# isolator.net
KiCad netlist of a schematic drawn in EAGLE
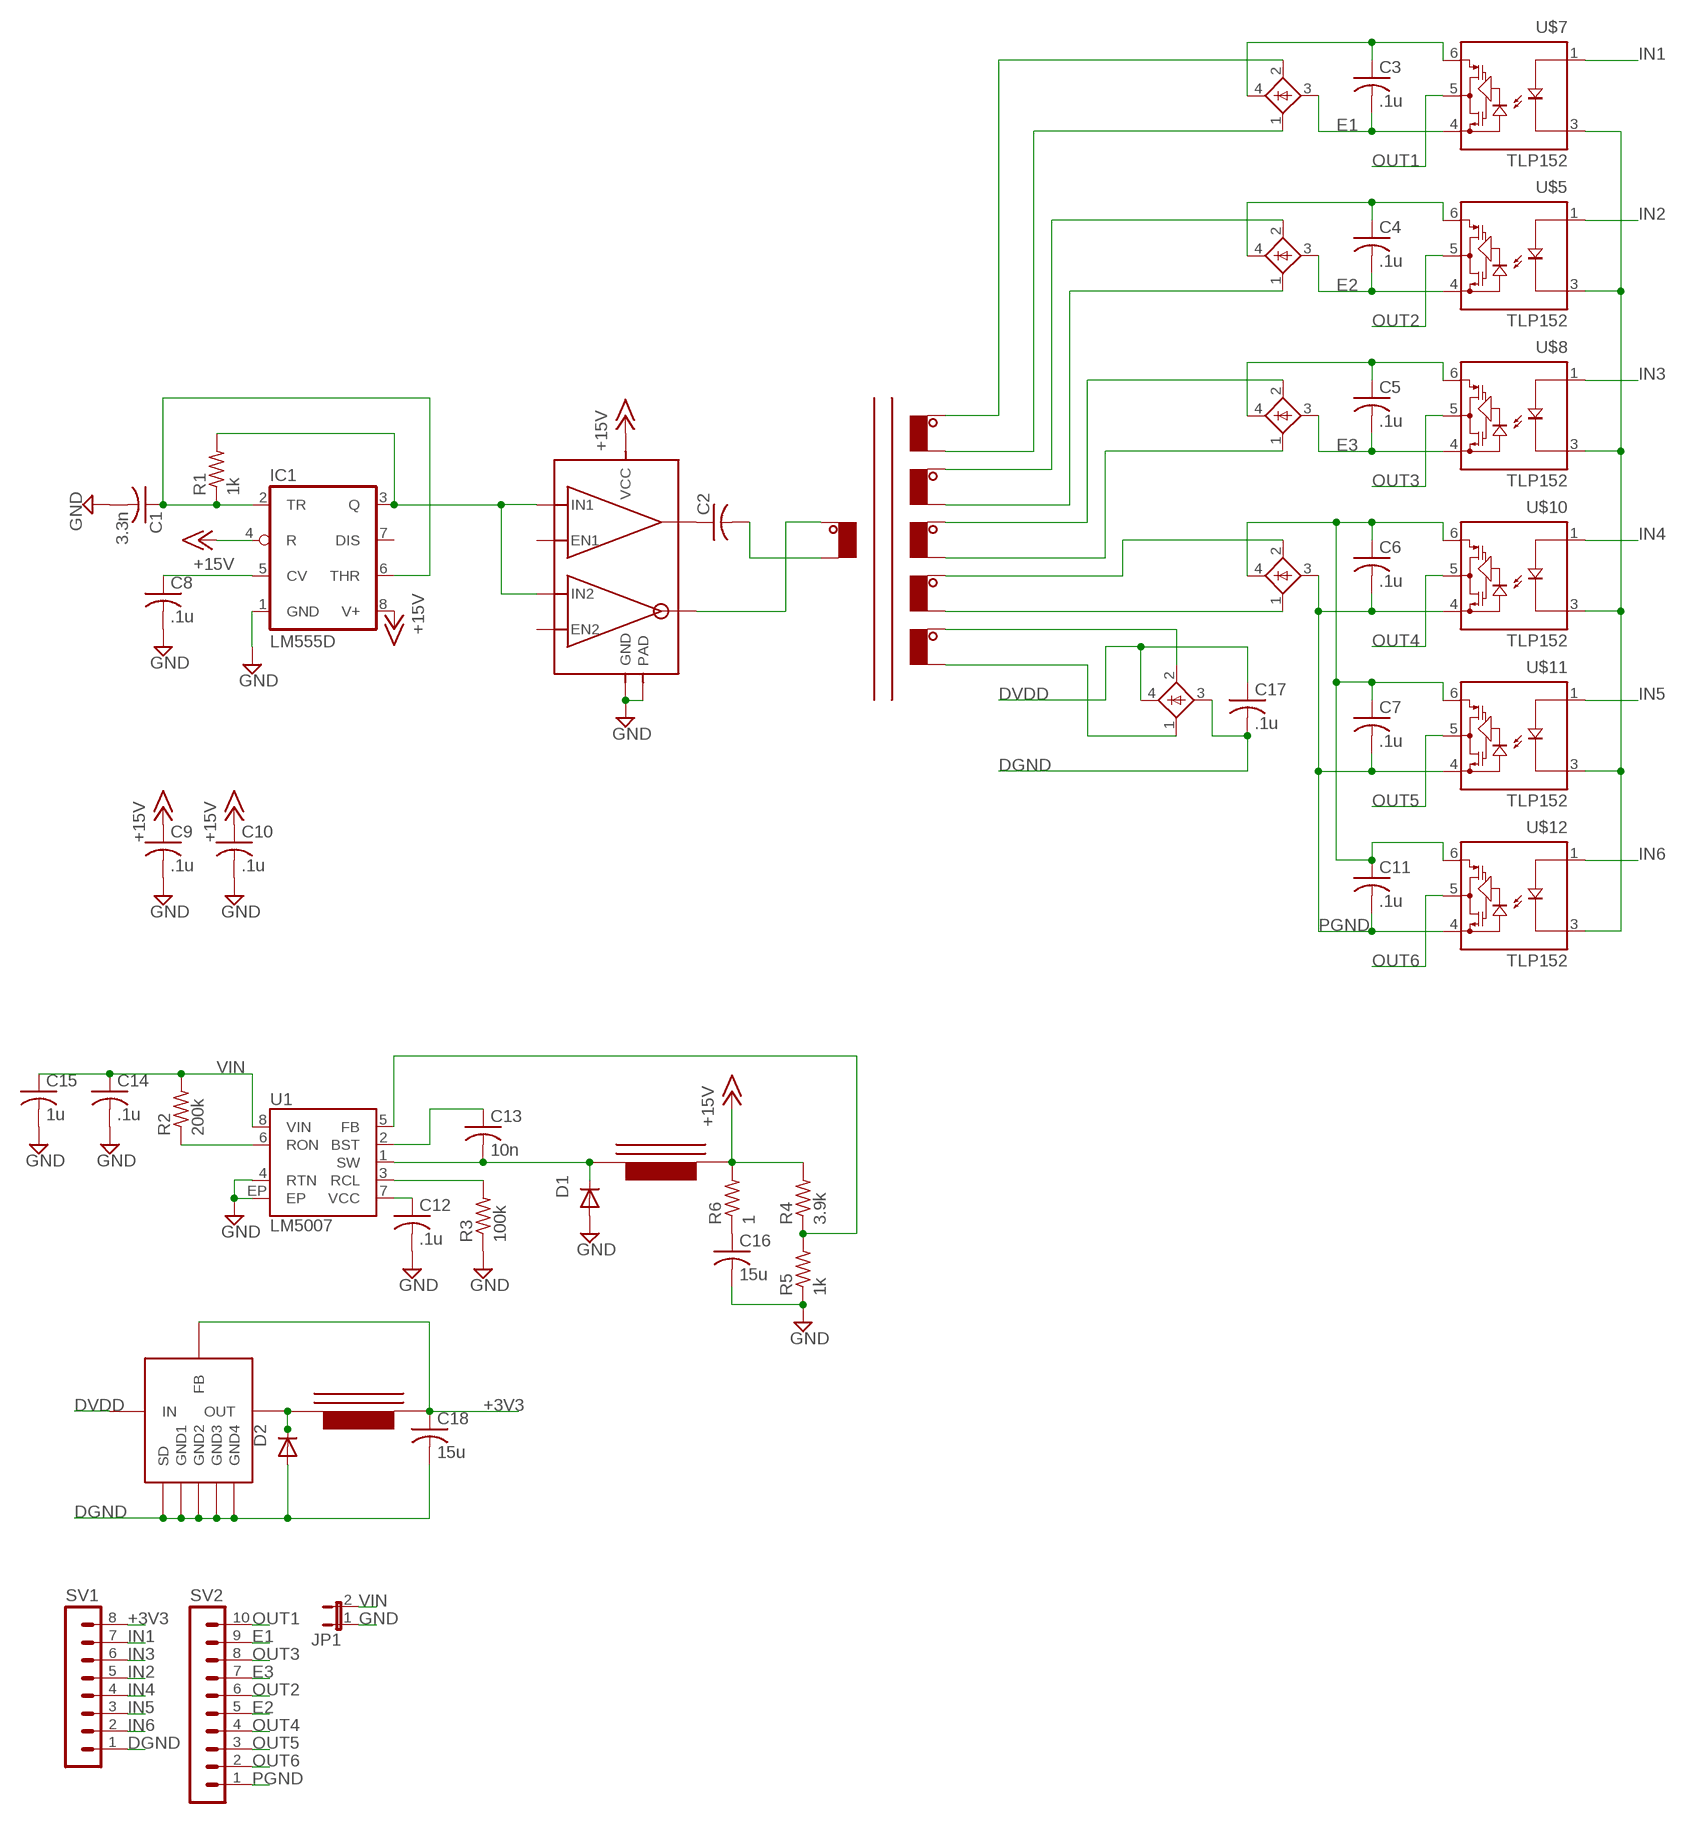
[diagram p0: schematic, sheet 1]
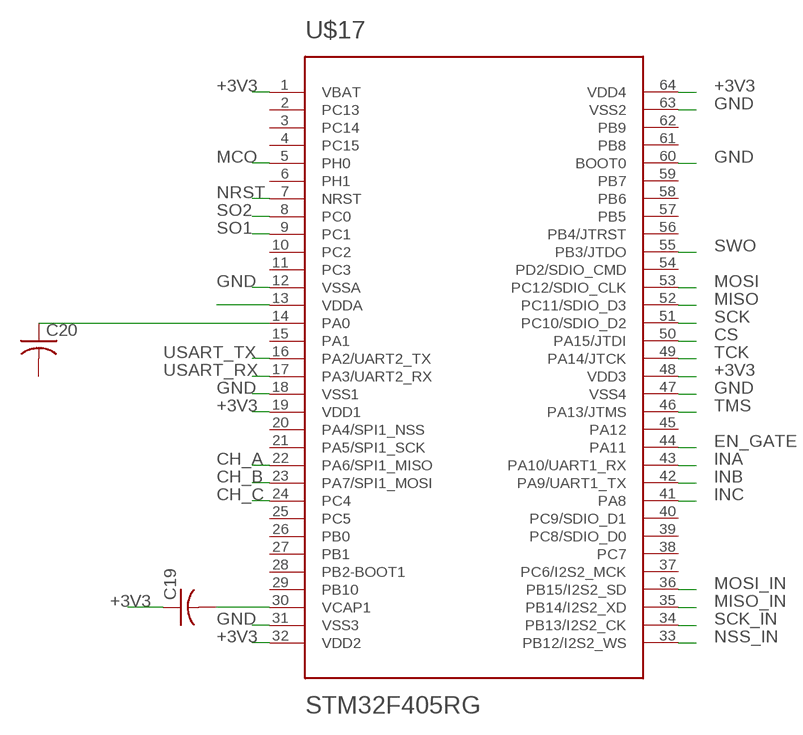
[diagram p1: schematic, sheet 2]

(export (version "E")
  (design (tool "Eeschema 10.0.6"))
  (components
    (comp (ref "C1")
      (value "3.3n")
      (footprint "eagle-import:C0805K")
      (libsource (lib "eagle-import") (part "rcl_C-USC0805K"))
    )
    (comp (ref "C2")
      (value "C-USC0805K")
      (footprint "eagle-import:C0805K")
      (libsource (lib "eagle-import") (part "rcl_C-USC0805K"))
    )
    (comp (ref "C3")
      (value ".1u")
      (footprint "eagle-import:C0805K")
      (libsource (lib "eagle-import") (part "rcl_C-USC0805K"))
    )
    (comp (ref "C4")
      (value ".1u")
      (footprint "eagle-import:C0805K")
      (libsource (lib "eagle-import") (part "rcl_C-USC0805K"))
    )
    (comp (ref "C5")
      (value ".1u")
      (footprint "eagle-import:C0805K")
      (libsource (lib "eagle-import") (part "rcl_C-USC0805K"))
    )
    (comp (ref "C6")
      (value ".1u")
      (footprint "eagle-import:C0805K")
      (libsource (lib "eagle-import") (part "rcl_C-USC0805K"))
    )
    (comp (ref "C7")
      (value ".1u")
      (footprint "eagle-import:C0805K")
      (libsource (lib "eagle-import") (part "rcl_C-USC0805K"))
    )
    (comp (ref "C8")
      (value ".1u")
      (footprint "eagle-import:C0805K")
      (libsource (lib "eagle-import") (part "rcl_C-USC0805K"))
    )
    (comp (ref "C9")
      (value ".1u")
      (footprint "eagle-import:C0805K")
      (libsource (lib "eagle-import") (part "rcl_C-USC0805K"))
    )
    (comp (ref "C10")
      (value ".1u")
      (footprint "eagle-import:C0805K")
      (libsource (lib "eagle-import") (part "rcl_C-USC0805K"))
    )
    (comp (ref "C11")
      (value ".1u")
      (footprint "eagle-import:C0805K")
      (libsource (lib "eagle-import") (part "rcl_C-USC0805K"))
    )
    (comp (ref "C12")
      (value ".1u")
      (footprint "eagle-import:C0805K")
      (libsource (lib "eagle-import") (part "rcl_C-USC0805K"))
    )
    (comp (ref "C13")
      (value "10n")
      (footprint "eagle-import:C0805K")
      (libsource (lib "eagle-import") (part "rcl_C-USC0805K"))
    )
    (comp (ref "C14")
      (value ".1u")
      (footprint "eagle-import:C0805K")
      (libsource (lib "eagle-import") (part "rcl_C-USC0805K"))
    )
    (comp (ref "C15")
      (value "1u")
      (footprint "eagle-import:C0805K")
      (libsource (lib "eagle-import") (part "rcl_C-USC0805K"))
    )
    (comp (ref "C16")
      (value "15u")
      (footprint "eagle-import:C0805K")
      (libsource (lib "eagle-import") (part "rcl_C-USC0805K"))
    )
    (comp (ref "C17")
      (value ".1u")
      (footprint "eagle-import:C0805K")
      (libsource (lib "eagle-import") (part "rcl_C-USC0805K"))
    )
    (comp (ref "C18")
      (value "15u")
      (footprint "eagle-import:C0805K")
      (libsource (lib "eagle-import") (part "rcl_C-USC0805K"))
    )
    (comp (ref "D1")
      (value "B170-13-F")
      (footprint "eagle-import:DO214AC")
      (libsource (lib "eagle-import") (part "DIODE-DO214AC"))
    )
    (comp (ref "D2")
      (value "B170-13-F")
      (footprint "eagle-import:DO214AC")
      (libsource (lib "eagle-import") (part "DIODE-DO214AC"))
    )
    (comp (ref "IC1")
      (value "LM555D")
      (footprint "eagle-import:SO08")
      (libsource (lib "eagle-import") (part "555DLM"))
    )
    (comp (ref "JP1")
      (value "JP1E")
      (footprint "eagle-import:JP1")
      (libsource (lib "eagle-import") (part "JP1E"))
    )
    (comp (ref "R1")
      (value "1k")
      (footprint "eagle-import:M0805")
      (libsource (lib "eagle-import") (part "R-US_M0805"))
    )
    (comp (ref "R2")
      (value "200k")
      (footprint "eagle-import:M0805")
      (libsource (lib "eagle-import") (part "R-US_M0805"))
    )
    (comp (ref "R3")
      (value "100k")
      (footprint "eagle-import:M0805")
      (libsource (lib "eagle-import") (part "R-US_M0805"))
    )
    (comp (ref "R4")
      (value "3.9k")
      (footprint "eagle-import:M0805")
      (libsource (lib "eagle-import") (part "R-US_M0805"))
    )
    (comp (ref "R5")
      (value "1k")
      (footprint "eagle-import:M0805")
      (libsource (lib "eagle-import") (part "R-US_M0805"))
    )
    (comp (ref "R6")
      (value "1")
      (footprint "eagle-import:M0805")
      (libsource (lib "eagle-import") (part "R-US_M0805"))
    )
    (comp (ref "SV1")
      (value "MA08-1")
      (footprint "eagle-import:MA08-1")
      (libsource (lib "eagle-import") (part "MA08-1"))
    )
    (comp (ref "SV2")
      (value "MA10-1")
      (footprint "eagle-import:MA10-1")
      (libsource (lib "eagle-import") (part "MA10-1"))
    )
    (comp (ref "U$1")
      (value "HP1")
      (footprint "eagle-import:HP1")
      (libsource (lib "eagle-import") (part "HP1"))
    )
    (comp (ref "U$2")
      (value "UCC27525DGN")
      (footprint "eagle-import:HTSSOP8DGN")
      (libsource (lib "eagle-import") (part "UCC27525DGN"))
    )
    (comp (ref "U$3")
      (value "BAS4002A")
      (footprint "eagle-import:SOT-143")
      (libsource (lib "eagle-import") (part "BAS4002A"))
    )
    (comp (ref "U$4")
      (value "BAS4002A")
      (footprint "eagle-import:SOT-143")
      (libsource (lib "eagle-import") (part "BAS4002A"))
    )
    (comp (ref "U$5")
      (value "TLP152")
      (footprint "eagle-import:DIP5-SMD")
      (libsource (lib "eagle-import") (part "TLP152"))
    )
    (comp (ref "U$6")
      (value "BAS4002A")
      (footprint "eagle-import:SOT-143")
      (libsource (lib "eagle-import") (part "BAS4002A"))
    )
    (comp (ref "U$7")
      (value "TLP152")
      (footprint "eagle-import:DIP5-SMD")
      (libsource (lib "eagle-import") (part "TLP152"))
    )
    (comp (ref "U$8")
      (value "TLP152")
      (footprint "eagle-import:DIP5-SMD")
      (libsource (lib "eagle-import") (part "TLP152"))
    )
    (comp (ref "U$9")
      (value "BAS4002A")
      (footprint "eagle-import:SOT-143")
      (libsource (lib "eagle-import") (part "BAS4002A"))
    )
    (comp (ref "U$10")
      (value "TLP152")
      (footprint "eagle-import:DIP5-SMD")
      (libsource (lib "eagle-import") (part "TLP152"))
    )
    (comp (ref "U$11")
      (value "TLP152")
      (footprint "eagle-import:DIP5-SMD")
      (libsource (lib "eagle-import") (part "TLP152"))
    )
    (comp (ref "U$12")
      (value "TLP152")
      (footprint "eagle-import:DIP5-SMD")
      (libsource (lib "eagle-import") (part "TLP152"))
    )
    (comp (ref "U$13")
      (value "SRN6045-101M")
      (footprint "eagle-import:SRN6045")
      (libsource (lib "eagle-import") (part "SRN6045-101M"))
    )
    (comp (ref "U$14")
      (value "BAS4002A")
      (footprint "eagle-import:SOT-143")
      (libsource (lib "eagle-import") (part "BAS4002A"))
    )
    (comp (ref "U$15")
      (value "AP1509")
      (footprint "eagle-import:SO8")
      (libsource (lib "eagle-import") (part "AP1509"))
    )
    (comp (ref "U$16")
      (value "SRN6045-101M")
      (footprint "eagle-import:SRN6045")
      (libsource (lib "eagle-import") (part "SRN6045-101M"))
    )
    (comp (ref "U1")
      (value "LM5007")
      (footprint "eagle-import:MSOP-8-EP")
      (libsource (lib "eagle-import") (part "LM5007"))
    )
    (comp (ref "C19")
      (value "C-USC0805K")
      (footprint "eagle-import:C0805K")
      (libsource (lib "eagle-import") (part "C-USC0805K"))
    )
    (comp (ref "C20")
      (value "C-USC0805K")
      (footprint "eagle-import:C0805K")
      (libsource (lib "eagle-import") (part "C-USC0805K"))
    )
    (comp (ref "U$17")
      (value "STM32F405RG")
      (footprint "eagle-import:TQFP64")
      (libsource (lib "eagle-import") (part "STM32F405RG"))
    )
  )
  (nets
    (net (code "1") (name "+3V3") (class "Default")
      (node (ref "C18") (pin "1") (pinfunction "1_1") (pintype "passive"))
      (node (ref "C19") (pin "1") (pinfunction "1_1") (pintype "passive"))
      (node (ref "SV1") (pin "8") (pinfunction "8_8") (pintype "passive"))
      (node (ref "U$15") (pin "3") (pinfunction "FB_3") (pintype "bidirectional"))
      (node (ref "U$16") (pin "P$2") (pinfunction "P$2_P$2") (pintype "bidirectional"))
      (node (ref "U$17") (pin "1") (pinfunction "VBAT_1") (pintype "bidirectional"))
      (node (ref "U$17") (pin "19") (pinfunction "VDD1_19") (pintype "bidirectional"))
      (node (ref "U$17") (pin "32") (pinfunction "VDD2_32") (pintype "bidirectional"))
      (node (ref "U$17") (pin "48") (pinfunction "VDD3_48") (pintype "bidirectional"))
      (node (ref "U$17") (pin "64") (pinfunction "VDD4_64") (pintype "bidirectional"))
    )
    (net (code "2") (name "+15V") (class "Default")
      (node (ref "C10") (pin "1") (pinfunction "1_1") (pintype "passive"))
      (node (ref "C9") (pin "1") (pinfunction "1_1") (pintype "passive"))
      (node (ref "IC1") (pin "4") (pinfunction "R_4") (pintype "input"))
      (node (ref "IC1") (pin "8") (pinfunction "V+_8") (pintype "power_in"))
      (node (ref "R4") (pin "2") (pinfunction "2_2") (pintype "passive"))
      (node (ref "R6") (pin "2") (pinfunction "2_2") (pintype "passive"))
      (node (ref "U$13") (pin "P$2") (pinfunction "P$2_P$2") (pintype "bidirectional"))
      (node (ref "U$2") (pin "6") (pinfunction "VCC_6") (pintype "bidirectional"))
    )
    (net (code "3") (name "CH_A") (class "Default")
      (node (ref "U$17") (pin "22") (pinfunction "PA6/SPI1_MISO_22") (pintype "bidirectional"))
    )
    (net (code "4") (name "CH_B") (class "Default")
      (node (ref "U$17") (pin "23") (pinfunction "PA7/SPI1_MOSI_23") (pintype "bidirectional"))
    )
    (net (code "5") (name "CH_C") (class "Default")
      (node (ref "U$17") (pin "24") (pinfunction "PC4_24") (pintype "bidirectional"))
    )
    (net (code "6") (name "CS") (class "Default")
      (node (ref "U$17") (pin "50") (pinfunction "PA15/JTDI_50") (pintype "bidirectional"))
    )
    (net (code "7") (name "DGND") (class "Default")
      (node (ref "C17") (pin "2") (pinfunction "2_2") (pintype "passive"))
      (node (ref "C18") (pin "2") (pinfunction "2_2") (pintype "passive"))
      (node (ref "D2") (pin "A") (pinfunction "A_A") (pintype "passive"))
      (node (ref "SV1") (pin "1") (pinfunction "1_1") (pintype "passive"))
      (node (ref "U$10") (pin "3") (pinfunction "LED-_3") (pintype "passive"))
      (node (ref "U$11") (pin "3") (pinfunction "LED-_3") (pintype "passive"))
      (node (ref "U$12") (pin "3") (pinfunction "LED-_3") (pintype "passive"))
      (node (ref "U$14") (pin "3") (pinfunction "-_3") (pintype "passive"))
      (node (ref "U$15") (pin "4") (pinfunction "SD_4") (pintype "bidirectional"))
      (node (ref "U$15") (pin "5") (pinfunction "GND1_5") (pintype "bidirectional"))
      (node (ref "U$15") (pin "6") (pinfunction "GND2_6") (pintype "bidirectional"))
      (node (ref "U$15") (pin "7") (pinfunction "GND3_7") (pintype "bidirectional"))
      (node (ref "U$15") (pin "8") (pinfunction "GND4_8") (pintype "bidirectional"))
      (node (ref "U$5") (pin "3") (pinfunction "LED-_3") (pintype "passive"))
      (node (ref "U$7") (pin "3") (pinfunction "LED-_3") (pintype "passive"))
      (node (ref "U$8") (pin "3") (pinfunction "LED-_3") (pintype "passive"))
    )
    (net (code "8") (name "DVDD") (class "Default")
      (node (ref "C17") (pin "1") (pinfunction "1_1") (pintype "passive"))
      (node (ref "U$14") (pin "4") (pinfunction "+_4") (pintype "passive"))
      (node (ref "U$15") (pin "1") (pinfunction "IN_1") (pintype "bidirectional"))
    )
    (net (code "9") (name "E1") (class "Default")
      (node (ref "C3") (pin "2") (pinfunction "2_2") (pintype "passive"))
      (node (ref "SV2") (pin "9") (pinfunction "9_9") (pintype "passive"))
      (node (ref "U$3") (pin "3") (pinfunction "-_3") (pintype "passive"))
      (node (ref "U$7") (pin "4") (pinfunction "GND_4") (pintype "passive"))
    )
    (net (code "10") (name "E2") (class "Default")
      (node (ref "C4") (pin "2") (pinfunction "2_2") (pintype "passive"))
      (node (ref "SV2") (pin "5") (pinfunction "5_5") (pintype "passive"))
      (node (ref "U$4") (pin "3") (pinfunction "-_3") (pintype "passive"))
      (node (ref "U$5") (pin "4") (pinfunction "GND_4") (pintype "passive"))
    )
    (net (code "11") (name "E3") (class "Default")
      (node (ref "C5") (pin "2") (pinfunction "2_2") (pintype "passive"))
      (node (ref "SV2") (pin "7") (pinfunction "7_7") (pintype "passive"))
      (node (ref "U$6") (pin "3") (pinfunction "-_3") (pintype "passive"))
      (node (ref "U$8") (pin "4") (pinfunction "GND_4") (pintype "passive"))
    )
    (net (code "12") (name "EN_GATE") (class "Default")
      (node (ref "U$17") (pin "44") (pinfunction "PA11_44") (pintype "bidirectional"))
    )
    (net (code "13") (name "GND") (class "Default")
      (node (ref "C1") (pin "2") (pinfunction "2_2") (pintype "passive"))
      (node (ref "C10") (pin "2") (pinfunction "2_2") (pintype "passive"))
      (node (ref "C12") (pin "2") (pinfunction "2_2") (pintype "passive"))
      (node (ref "C14") (pin "2") (pinfunction "2_2") (pintype "passive"))
      (node (ref "C15") (pin "2") (pinfunction "2_2") (pintype "passive"))
      (node (ref "C16") (pin "2") (pinfunction "2_2") (pintype "passive"))
      (node (ref "C8") (pin "2") (pinfunction "2_2") (pintype "passive"))
      (node (ref "C9") (pin "2") (pinfunction "2_2") (pintype "passive"))
      (node (ref "D1") (pin "A") (pinfunction "A_A") (pintype "passive"))
      (node (ref "IC1") (pin "1") (pinfunction "GND_1") (pintype "power_in"))
      (node (ref "JP1") (pin "1") (pinfunction "1_1") (pintype "passive"))
      (node (ref "R3") (pin "1") (pinfunction "1_1") (pintype "passive"))
      (node (ref "R5") (pin "1") (pinfunction "1_1") (pintype "passive"))
      (node (ref "U$17") (pin "12") (pinfunction "VSSA_12") (pintype "bidirectional"))
      (node (ref "U$17") (pin "18") (pinfunction "VSS1_18") (pintype "bidirectional"))
      (node (ref "U$17") (pin "31") (pinfunction "VSS3_31") (pintype "bidirectional"))
      (node (ref "U$17") (pin "47") (pinfunction "VSS4_47") (pintype "bidirectional"))
      (node (ref "U$17") (pin "60") (pinfunction "BOOT0_60") (pintype "bidirectional"))
      (node (ref "U$17") (pin "63") (pinfunction "VSS2_63") (pintype "bidirectional"))
      (node (ref "U$2") (pin "3") (pinfunction "GND_3") (pintype "bidirectional"))
      (node (ref "U$2") (pin "EXP") (pinfunction "PAD_EXP") (pintype "bidirectional"))
      (node (ref "U1") (pin "4") (pinfunction "RTN_4") (pintype "bidirectional"))
      (node (ref "U1") (pin "EP") (pinfunction "EP_EP") (pintype "bidirectional"))
    )
    (net (code "14") (name "IN1") (class "Default")
      (node (ref "SV1") (pin "7") (pinfunction "7_7") (pintype "passive"))
      (node (ref "U$7") (pin "1") (pinfunction "LED+_1") (pintype "passive"))
    )
    (net (code "15") (name "IN2") (class "Default")
      (node (ref "SV1") (pin "5") (pinfunction "5_5") (pintype "passive"))
      (node (ref "U$5") (pin "1") (pinfunction "LED+_1") (pintype "passive"))
    )
    (net (code "16") (name "IN3") (class "Default")
      (node (ref "SV1") (pin "6") (pinfunction "6_6") (pintype "passive"))
      (node (ref "U$8") (pin "1") (pinfunction "LED+_1") (pintype "passive"))
    )
    (net (code "17") (name "IN4") (class "Default")
      (node (ref "SV1") (pin "4") (pinfunction "4_4") (pintype "passive"))
      (node (ref "U$10") (pin "1") (pinfunction "LED+_1") (pintype "passive"))
    )
    (net (code "18") (name "IN5") (class "Default")
      (node (ref "SV1") (pin "3") (pinfunction "3_3") (pintype "passive"))
      (node (ref "U$11") (pin "1") (pinfunction "LED+_1") (pintype "passive"))
    )
    (net (code "19") (name "IN6") (class "Default")
      (node (ref "SV1") (pin "2") (pinfunction "2_2") (pintype "passive"))
      (node (ref "U$12") (pin "1") (pinfunction "LED+_1") (pintype "passive"))
    )
    (net (code "20") (name "INA") (class "Default")
      (node (ref "U$17") (pin "43") (pinfunction "PA10/UART1_RX_43") (pintype "bidirectional"))
    )
    (net (code "21") (name "INB") (class "Default")
      (node (ref "U$17") (pin "42") (pinfunction "PA9/UART1_TX_42") (pintype "bidirectional"))
    )
    (net (code "22") (name "INC") (class "Default")
      (node (ref "U$17") (pin "41") (pinfunction "PA8_41") (pintype "bidirectional"))
    )
    (net (code "23") (name "MCO") (class "Default")
      (node (ref "U$17") (pin "5") (pinfunction "PH0_5") (pintype "bidirectional"))
    )
    (net (code "24") (name "MISO") (class "Default")
      (node (ref "U$17") (pin "52") (pinfunction "PC11/SDIO_D3_52") (pintype "bidirectional"))
    )
    (net (code "25") (name "MISO_IN") (class "Default")
      (node (ref "U$17") (pin "35") (pinfunction "PB14/I2S2_XD_35") (pintype "bidirectional"))
    )
    (net (code "26") (name "MOSI") (class "Default")
      (node (ref "U$17") (pin "53") (pinfunction "PC12/SDIO_CLK_53") (pintype "bidirectional"))
    )
    (net (code "27") (name "MOSI_IN") (class "Default")
      (node (ref "U$17") (pin "36") (pinfunction "PB15/I2S2_SD_36") (pintype "bidirectional"))
    )
    (net (code "28") (name "NRST") (class "Default")
      (node (ref "U$17") (pin "7") (pinfunction "NRST_7") (pintype "bidirectional"))
    )
    (net (code "29") (name "NSS_IN") (class "Default")
      (node (ref "U$17") (pin "33") (pinfunction "PB12/I2S2_WS_33") (pintype "bidirectional"))
    )
    (net (code "30") (name "Net-(C16-Pad1)") (class "Default")
      (node (ref "C16") (pin "1") (pinfunction "1_1") (pintype "passive"))
      (node (ref "R6") (pin "1") (pinfunction "1_1") (pintype "passive"))
    )
    (net (code "31") (name "Net-(IC1-CV)") (class "Default")
      (node (ref "C8") (pin "1") (pinfunction "1_1") (pintype "passive"))
      (node (ref "IC1") (pin "5") (pinfunction "CV_5") (pintype "input"))
    )
    (net (code "32") (name "Net-(IC1-Q)") (class "Default")
      (node (ref "IC1") (pin "3") (pinfunction "Q_3") (pintype "output"))
      (node (ref "R1") (pin "2") (pinfunction "2_2") (pintype "passive"))
      (node (ref "U$2") (pin "2") (pinfunction "IN1_2") (pintype "bidirectional"))
      (node (ref "U$2") (pin "4") (pinfunction "IN2_4") (pintype "bidirectional"))
    )
    (net (code "33") (name "Net-(IC1-THR)") (class "Default")
      (node (ref "C1") (pin "1") (pinfunction "1_1") (pintype "passive"))
      (node (ref "IC1") (pin "2") (pinfunction "TR_2") (pintype "input"))
      (node (ref "IC1") (pin "6") (pinfunction "THR_6") (pintype "input"))
      (node (ref "R1") (pin "1") (pinfunction "1_1") (pintype "passive"))
    )
    (net (code "34") (name "Net-(U$1-1A)") (class "Default")
      (node (ref "U$1") (pin "P$4") (pinfunction "1A_P$4") (pintype "bidirectional"))
      (node (ref "U$2") (pin "5") (pinfunction "OUT2_5") (pintype "bidirectional"))
    )
    (net (code "35") (name "Net-(U$1-1B)") (class "Default")
      (node (ref "C2") (pin "2") (pinfunction "2_2") (pintype "passive"))
      (node (ref "U$1") (pin "P$1") (pinfunction "1B_P$1") (pintype "bidirectional"))
    )
    (net (code "36") (name "Net-(U$1-2A)") (class "Default")
      (node (ref "U$1") (pin "P$5") (pinfunction "2A_P$5") (pintype "bidirectional"))
      (node (ref "U$14") (pin "2") (pinfunction "AC2_2") (pintype "passive"))
    )
    (net (code "37") (name "Net-(U$1-2B)") (class "Default")
      (node (ref "U$1") (pin "P$2") (pinfunction "2B_P$2") (pintype "bidirectional"))
      (node (ref "U$14") (pin "1") (pinfunction "AC1_1") (pintype "passive"))
    )
    (net (code "38") (name "Net-(U$1-3A)") (class "Default")
      (node (ref "U$1") (pin "P$6") (pinfunction "3A_P$6") (pintype "bidirectional"))
      (node (ref "U$3") (pin "2") (pinfunction "AC2_2") (pintype "passive"))
    )
    (net (code "39") (name "Net-(U$1-3B)") (class "Default")
      (node (ref "U$1") (pin "P$3") (pinfunction "3B_P$3") (pintype "bidirectional"))
      (node (ref "U$3") (pin "1") (pinfunction "AC1_1") (pintype "passive"))
    )
    (net (code "40") (name "Net-(U$1-4A)") (class "Default")
      (node (ref "U$1") (pin "P$10") (pinfunction "4A_P$10") (pintype "bidirectional"))
      (node (ref "U$4") (pin "2") (pinfunction "AC2_2") (pintype "passive"))
    )
    (net (code "41") (name "Net-(U$1-4B)") (class "Default")
      (node (ref "U$1") (pin "P$7") (pinfunction "4B_P$7") (pintype "bidirectional"))
      (node (ref "U$4") (pin "1") (pinfunction "AC1_1") (pintype "passive"))
    )
    (net (code "42") (name "Net-(U$1-5A)") (class "Default")
      (node (ref "U$1") (pin "P$11") (pinfunction "5A_P$11") (pintype "bidirectional"))
      (node (ref "U$6") (pin "2") (pinfunction "AC2_2") (pintype "passive"))
    )
    (net (code "43") (name "Net-(U$1-5B)") (class "Default")
      (node (ref "U$1") (pin "P$8") (pinfunction "5B_P$8") (pintype "bidirectional"))
      (node (ref "U$6") (pin "1") (pinfunction "AC1_1") (pintype "passive"))
    )
    (net (code "44") (name "Net-(U$1-6A)") (class "Default")
      (node (ref "U$1") (pin "P$12") (pinfunction "6A_P$12") (pintype "bidirectional"))
      (node (ref "U$9") (pin "2") (pinfunction "AC2_2") (pintype "passive"))
    )
    (net (code "45") (name "Net-(U$1-6B)") (class "Default")
      (node (ref "U$1") (pin "P$9") (pinfunction "6B_P$9") (pintype "bidirectional"))
      (node (ref "U$9") (pin "1") (pinfunction "AC1_1") (pintype "passive"))
    )
    (net (code "46") (name "Net-(U$2-OUT1)") (class "Default")
      (node (ref "C2") (pin "1") (pinfunction "1_1") (pintype "passive"))
      (node (ref "U$2") (pin "7") (pinfunction "OUT1_7") (pintype "bidirectional"))
    )
    (net (code "47") (name "Net-(U$3-+)") (class "Default")
      (node (ref "C3") (pin "1") (pinfunction "1_1") (pintype "passive"))
      (node (ref "U$3") (pin "4") (pinfunction "+_4") (pintype "passive"))
      (node (ref "U$7") (pin "6") (pinfunction "VDD_6") (pintype "passive"))
    )
    (net (code "48") (name "Net-(U$4-+)") (class "Default")
      (node (ref "C4") (pin "1") (pinfunction "1_1") (pintype "passive"))
      (node (ref "U$4") (pin "4") (pinfunction "+_4") (pintype "passive"))
      (node (ref "U$5") (pin "6") (pinfunction "VDD_6") (pintype "passive"))
    )
    (net (code "49") (name "Net-(U$6-+)") (class "Default")
      (node (ref "C5") (pin "1") (pinfunction "1_1") (pintype "passive"))
      (node (ref "U$6") (pin "4") (pinfunction "+_4") (pintype "passive"))
      (node (ref "U$8") (pin "6") (pinfunction "VDD_6") (pintype "passive"))
    )
    (net (code "50") (name "Net-(U$10-VDD)") (class "Default")
      (node (ref "C11") (pin "1") (pinfunction "1_1") (pintype "passive"))
      (node (ref "C6") (pin "1") (pinfunction "1_1") (pintype "passive"))
      (node (ref "C7") (pin "1") (pinfunction "1_1") (pintype "passive"))
      (node (ref "U$10") (pin "6") (pinfunction "VDD_6") (pintype "passive"))
      (node (ref "U$11") (pin "6") (pinfunction "VDD_6") (pintype "passive"))
      (node (ref "U$12") (pin "6") (pinfunction "VDD_6") (pintype "passive"))
      (node (ref "U$9") (pin "4") (pinfunction "+_4") (pintype "passive"))
    )
    (net (code "51") (name "Net-(U$15-OUT)") (class "Default")
      (node (ref "D2") (pin "C") (pinfunction "C_C") (pintype "passive"))
      (node (ref "U$15") (pin "2") (pinfunction "OUT_2") (pintype "bidirectional"))
      (node (ref "U$16") (pin "P$1") (pinfunction "P$1_P$1") (pintype "bidirectional"))
    )
    (net (code "52") (name "Net-(U$17-PA0)") (class "Default")
      (node (ref "C20") (pin "1") (pinfunction "1_1") (pintype "passive"))
      (node (ref "U$17") (pin "14") (pinfunction "PA0_14") (pintype "bidirectional"))
    )
    (net (code "53") (name "Net-(U$17-VCAP1)") (class "Default")
      (node (ref "C19") (pin "2") (pinfunction "2_2") (pintype "passive"))
      (node (ref "U$17") (pin "30") (pinfunction "VCAP1_30") (pintype "bidirectional"))
    )
    (net (code "54") (name "Net-(U1-BST)") (class "Default")
      (node (ref "C13") (pin "1") (pinfunction "1_1") (pintype "passive"))
      (node (ref "U1") (pin "2") (pinfunction "BST_2") (pintype "bidirectional"))
    )
    (net (code "55") (name "Net-(U1-FB)") (class "Default")
      (node (ref "R4") (pin "1") (pinfunction "1_1") (pintype "passive"))
      (node (ref "R5") (pin "2") (pinfunction "2_2") (pintype "passive"))
      (node (ref "U1") (pin "5") (pinfunction "FB_5") (pintype "bidirectional"))
    )
    (net (code "56") (name "Net-(U1-RCL)") (class "Default")
      (node (ref "R3") (pin "2") (pinfunction "2_2") (pintype "passive"))
      (node (ref "U1") (pin "3") (pinfunction "RCL_3") (pintype "bidirectional"))
    )
    (net (code "57") (name "Net-(U1-RON)") (class "Default")
      (node (ref "R2") (pin "1") (pinfunction "1_1") (pintype "passive"))
      (node (ref "U1") (pin "6") (pinfunction "RON_6") (pintype "bidirectional"))
    )
    (net (code "58") (name "Net-(U1-SW)") (class "Default")
      (node (ref "C13") (pin "2") (pinfunction "2_2") (pintype "passive"))
      (node (ref "D1") (pin "C") (pinfunction "C_C") (pintype "passive"))
      (node (ref "U$13") (pin "P$1") (pinfunction "P$1_P$1") (pintype "bidirectional"))
      (node (ref "U1") (pin "1") (pinfunction "SW_1") (pintype "bidirectional"))
    )
    (net (code "59") (name "Net-(U1-VCC)") (class "Default")
      (node (ref "C12") (pin "1") (pinfunction "1_1") (pintype "passive"))
      (node (ref "U1") (pin "7") (pinfunction "VCC_7") (pintype "bidirectional"))
    )
    (net (code "60") (name "OUT1") (class "Default")
      (node (ref "SV2") (pin "10") (pinfunction "10_10") (pintype "passive"))
      (node (ref "U$7") (pin "5") (pinfunction "VO_5") (pintype "passive"))
    )
    (net (code "61") (name "OUT2") (class "Default")
      (node (ref "SV2") (pin "6") (pinfunction "6_6") (pintype "passive"))
      (node (ref "U$5") (pin "5") (pinfunction "VO_5") (pintype "passive"))
    )
    (net (code "62") (name "OUT3") (class "Default")
      (node (ref "SV2") (pin "8") (pinfunction "8_8") (pintype "passive"))
      (node (ref "U$8") (pin "5") (pinfunction "VO_5") (pintype "passive"))
    )
    (net (code "63") (name "OUT4") (class "Default")
      (node (ref "SV2") (pin "4") (pinfunction "4_4") (pintype "passive"))
      (node (ref "U$10") (pin "5") (pinfunction "VO_5") (pintype "passive"))
    )
    (net (code "64") (name "OUT5") (class "Default")
      (node (ref "SV2") (pin "3") (pinfunction "3_3") (pintype "passive"))
      (node (ref "U$11") (pin "5") (pinfunction "VO_5") (pintype "passive"))
    )
    (net (code "65") (name "OUT6") (class "Default")
      (node (ref "SV2") (pin "2") (pinfunction "2_2") (pintype "passive"))
      (node (ref "U$12") (pin "5") (pinfunction "VO_5") (pintype "passive"))
    )
    (net (code "66") (name "PGND") (class "Default")
      (node (ref "C11") (pin "2") (pinfunction "2_2") (pintype "passive"))
      (node (ref "C6") (pin "2") (pinfunction "2_2") (pintype "passive"))
      (node (ref "C7") (pin "2") (pinfunction "2_2") (pintype "passive"))
      (node (ref "SV2") (pin "1") (pinfunction "1_1") (pintype "passive"))
      (node (ref "U$10") (pin "4") (pinfunction "GND_4") (pintype "passive"))
      (node (ref "U$11") (pin "4") (pinfunction "GND_4") (pintype "passive"))
      (node (ref "U$12") (pin "4") (pinfunction "GND_4") (pintype "passive"))
      (node (ref "U$9") (pin "3") (pinfunction "-_3") (pintype "passive"))
    )
    (net (code "67") (name "SCK") (class "Default")
      (node (ref "U$17") (pin "51") (pinfunction "PC10/SDIO_D2_51") (pintype "bidirectional"))
    )
    (net (code "68") (name "SCK_IN") (class "Default")
      (node (ref "U$17") (pin "34") (pinfunction "PB13/I2S2_CK_34") (pintype "bidirectional"))
    )
    (net (code "69") (name "SO1") (class "Default")
      (node (ref "U$17") (pin "9") (pinfunction "PC1_9") (pintype "bidirectional"))
    )
    (net (code "70") (name "SO2") (class "Default")
      (node (ref "U$17") (pin "8") (pinfunction "PC0_8") (pintype "bidirectional"))
    )
    (net (code "71") (name "SWO") (class "Default")
      (node (ref "U$17") (pin "55") (pinfunction "PB3/JTDO_55") (pintype "bidirectional"))
    )
    (net (code "72") (name "TCK") (class "Default")
      (node (ref "U$17") (pin "49") (pinfunction "PA14/JTCK_49") (pintype "bidirectional"))
    )
    (net (code "73") (name "TMS") (class "Default")
      (node (ref "U$17") (pin "46") (pinfunction "PA13/JTMS_46") (pintype "bidirectional"))
    )
    (net (code "74") (name "USART_RX") (class "Default")
      (node (ref "U$17") (pin "17") (pinfunction "PA3/UART2_RX_17") (pintype "bidirectional"))
    )
    (net (code "75") (name "USART_TX") (class "Default")
      (node (ref "U$17") (pin "16") (pinfunction "PA2/UART2_TX_16") (pintype "bidirectional"))
    )
    (net (code "76") (name "VIN") (class "Default")
      (node (ref "C14") (pin "1") (pinfunction "1_1") (pintype "passive"))
      (node (ref "C15") (pin "1") (pinfunction "1_1") (pintype "passive"))
      (node (ref "JP1") (pin "2") (pinfunction "2_2") (pintype "passive"))
      (node (ref "R2") (pin "2") (pinfunction "2_2") (pintype "passive"))
      (node (ref "U1") (pin "8") (pinfunction "VIN_8") (pintype "bidirectional"))
    )
    (net (code "77") (name "unconnected-(C20-Pad2)") (class "Default")
      (node (ref "C20") (pin "2") (pinfunction "2_2") (pintype "passive"))
    )
    (net (code "78") (name "unconnected-(IC1-DIS-Pad7)") (class "Default")
      (node (ref "IC1") (pin "7") (pinfunction "DIS_7") (pintype "input"))
    )
    (net (code "79") (name "unconnected-(U$2-EN1-Pad1)") (class "Default")
      (node (ref "U$2") (pin "1") (pinfunction "EN1_1") (pintype "bidirectional"))
    )
    (net (code "80") (name "unconnected-(U$2-EN2-Pad8)") (class "Default")
      (node (ref "U$2") (pin "8") (pinfunction "EN2_8") (pintype "bidirectional"))
    )
    (net (code "81") (name "unconnected-(U$17-PA1-Pad15)") (class "Default")
      (node (ref "U$17") (pin "15") (pinfunction "PA1_15") (pintype "bidirectional"))
    )
    (net (code "82") (name "unconnected-(U$17-PA4{slash}SPI1_NSS-Pad20)") (class "Default")
      (node (ref "U$17") (pin "20") (pinfunction "PA4/SPI1_NSS_20") (pintype "bidirectional"))
    )
    (net (code "83") (name "unconnected-(U$17-PA5{slash}SPI1_SCK-Pad21)") (class "Default")
      (node (ref "U$17") (pin "21") (pinfunction "PA5/SPI1_SCK_21") (pintype "bidirectional"))
    )
    (net (code "84") (name "unconnected-(U$17-PA12-Pad45)") (class "Default")
      (node (ref "U$17") (pin "45") (pinfunction "PA12_45") (pintype "bidirectional"))
    )
    (net (code "85") (name "unconnected-(U$17-PB0-Pad26)") (class "Default")
      (node (ref "U$17") (pin "26") (pinfunction "PB0_26") (pintype "bidirectional"))
    )
    (net (code "86") (name "unconnected-(U$17-PB1-Pad27)") (class "Default")
      (node (ref "U$17") (pin "27") (pinfunction "PB1_27") (pintype "bidirectional"))
    )
    (net (code "87") (name "unconnected-(U$17-PB2-BOOT1-Pad28)") (class "Default")
      (node (ref "U$17") (pin "28") (pinfunction "PB2-BOOT1_28") (pintype "bidirectional"))
    )
    (net (code "88") (name "unconnected-(U$17-PB4{slash}JTRST-Pad56)") (class "Default")
      (node (ref "U$17") (pin "56") (pinfunction "PB4/JTRST_56") (pintype "bidirectional"))
    )
    (net (code "89") (name "unconnected-(U$17-PB5-Pad57)") (class "Default")
      (node (ref "U$17") (pin "57") (pinfunction "PB5_57") (pintype "bidirectional"))
    )
    (net (code "90") (name "unconnected-(U$17-PB6-Pad58)") (class "Default")
      (node (ref "U$17") (pin "58") (pinfunction "PB6_58") (pintype "bidirectional"))
    )
    (net (code "91") (name "unconnected-(U$17-PB7-Pad59)") (class "Default")
      (node (ref "U$17") (pin "59") (pinfunction "PB7_59") (pintype "bidirectional"))
    )
    (net (code "92") (name "unconnected-(U$17-PB8-Pad61)") (class "Default")
      (node (ref "U$17") (pin "61") (pinfunction "PB8_61") (pintype "bidirectional"))
    )
    (net (code "93") (name "unconnected-(U$17-PB9-Pad62)") (class "Default")
      (node (ref "U$17") (pin "62") (pinfunction "PB9_62") (pintype "bidirectional"))
    )
    (net (code "94") (name "unconnected-(U$17-PB10-Pad29)") (class "Default")
      (node (ref "U$17") (pin "29") (pinfunction "PB10_29") (pintype "bidirectional"))
    )
    (net (code "95") (name "unconnected-(U$17-PC2-Pad10)") (class "Default")
      (node (ref "U$17") (pin "10") (pinfunction "PC2_10") (pintype "bidirectional"))
    )
    (net (code "96") (name "unconnected-(U$17-PC3-Pad11)") (class "Default")
      (node (ref "U$17") (pin "11") (pinfunction "PC3_11") (pintype "bidirectional"))
    )
    (net (code "97") (name "unconnected-(U$17-PC5-Pad25)") (class "Default")
      (node (ref "U$17") (pin "25") (pinfunction "PC5_25") (pintype "bidirectional"))
    )
    (net (code "98") (name "unconnected-(U$17-PC6{slash}I2S2_MCK-Pad37)") (class "Default")
      (node (ref "U$17") (pin "37") (pinfunction "PC6/I2S2_MCK_37") (pintype "bidirectional"))
    )
    (net (code "99") (name "unconnected-(U$17-PC7-Pad38)") (class "Default")
      (node (ref "U$17") (pin "38") (pinfunction "PC7_38") (pintype "bidirectional"))
    )
    (net (code "100") (name "unconnected-(U$17-PC8{slash}SDIO_D0-Pad39)") (class "Default")
      (node (ref "U$17") (pin "39") (pinfunction "PC8/SDIO_D0_39") (pintype "bidirectional"))
    )
    (net (code "101") (name "unconnected-(U$17-PC9{slash}SDIO_D1-Pad40)") (class "Default")
      (node (ref "U$17") (pin "40") (pinfunction "PC9/SDIO_D1_40") (pintype "bidirectional"))
    )
    (net (code "102") (name "unconnected-(U$17-PC13-Pad2)") (class "Default")
      (node (ref "U$17") (pin "2") (pinfunction "PC13_2") (pintype "bidirectional"))
    )
    (net (code "103") (name "unconnected-(U$17-PC14-Pad3)") (class "Default")
      (node (ref "U$17") (pin "3") (pinfunction "PC14_3") (pintype "bidirectional"))
    )
    (net (code "104") (name "unconnected-(U$17-PC15-Pad4)") (class "Default")
      (node (ref "U$17") (pin "4") (pinfunction "PC15_4") (pintype "bidirectional"))
    )
    (net (code "105") (name "unconnected-(U$17-PD2{slash}SDIO_CMD-Pad54)") (class "Default")
      (node (ref "U$17") (pin "54") (pinfunction "PD2/SDIO_CMD_54") (pintype "bidirectional"))
    )
    (net (code "106") (name "unconnected-(U$17-PH1-Pad6)") (class "Default")
      (node (ref "U$17") (pin "6") (pinfunction "PH1_6") (pintype "bidirectional"))
    )
    (net (code "107") (name "unconnected-(U$17-VDDA-Pad13)") (class "Default")
      (node (ref "U$17") (pin "13") (pinfunction "VDDA_13") (pintype "bidirectional"))
    )
  )
)
